# MainShunt.net
KiCad netlist of a schematic drawn in Altium Designer
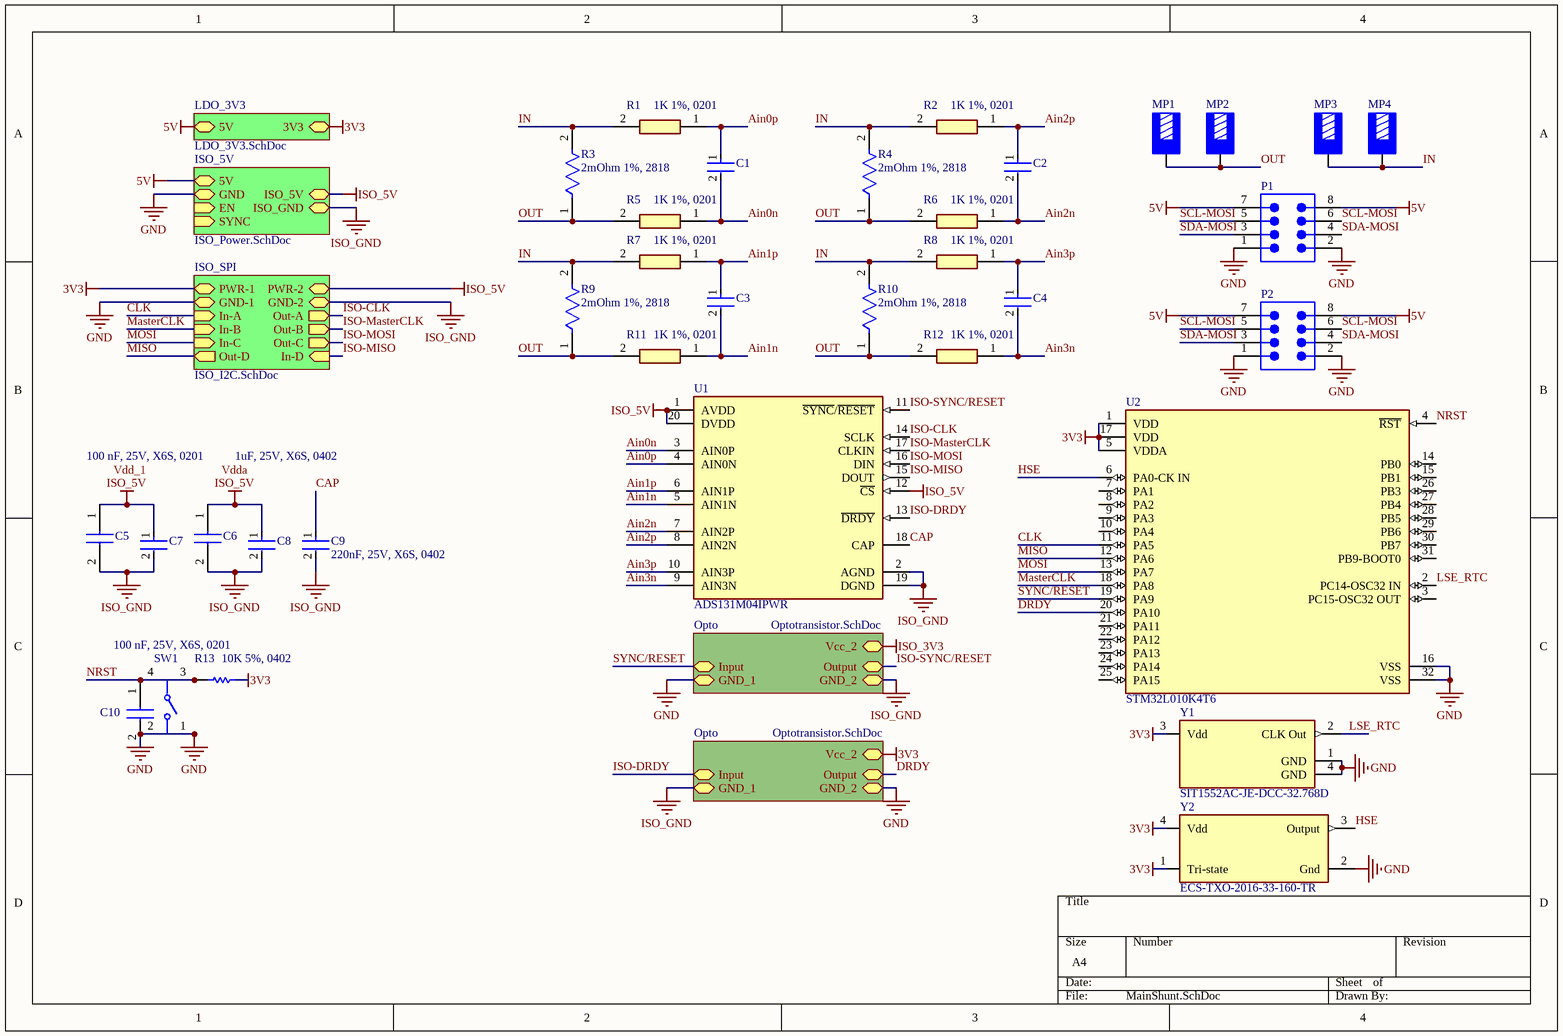
[diagram p0: MainShunt.SchDoc]

(export (version "E")
  (design (tool "Eeschema 10.0.6"))
  (components
    (comp (ref "C1")
      (value "10nF, 25V, X5R, 0201")
      (footprint "FP-GRM033-0_03-IPC_C")
      (description "Chip Multilayer Ceramic Capacitors for General Purpose, 0201, 10000pF, X5R, 15%, 10%, 25V")
      (fields (field (name "TOLERANCE") "10%") (field (name "VOLTAGE") "25V"))
      (libsource (lib "Altium Content Vault") (part "b4654b650e69147ec39a6b967a45e02"))
    )
    (comp (ref "C2")
      (value "10nF, 25V, X5R, 0201")
      (footprint "FP-GRM033-0_03-IPC_C")
      (description "Chip Multilayer Ceramic Capacitors for General Purpose, 0201, 10000pF, X5R, 15%, 10%, 25V")
      (fields (field (name "TOLERANCE") "10%") (field (name "VOLTAGE") "25V"))
      (libsource (lib "Altium Content Vault") (part "b4654b650e69147ec39a6b967a45e02"))
    )
    (comp (ref "C3")
      (value "10nF, 25V, X5R, 0201")
      (footprint "FP-GRM033-0_03-IPC_C")
      (description "Chip Multilayer Ceramic Capacitors for General Purpose, 0201, 10000pF, X5R, 15%, 10%, 25V")
      (fields (field (name "TOLERANCE") "10%") (field (name "VOLTAGE") "25V"))
      (libsource (lib "Altium Content Vault") (part "b4654b650e69147ec39a6b967a45e02"))
    )
    (comp (ref "C4")
      (value "10nF, 25V, X5R, 0201")
      (footprint "FP-GRM033-0_03-IPC_C")
      (description "Chip Multilayer Ceramic Capacitors for General Purpose, 0201, 10000pF, X5R, 15%, 10%, 25V")
      (fields (field (name "TOLERANCE") "10%") (field (name "VOLTAGE") "25V"))
      (libsource (lib "Altium Content Vault") (part "b4654b650e69147ec39a6b967a45e02"))
    )
    (comp (ref "C5")
      (value "100 nF, 25V, X6S, 0201")
      (footprint "SamacSys:CAPC0603X33N")
      (description "Capacitor")
      (fields
        (field (name "MANUFACTURER_PART_NUMBER") "GRM033C81E104KE14D")
        (field (name "MOUSER PART NUMBER") "81-GRM33C81E104KE14D")
      )
      (libsource (lib "*") (part "GRM033C81E104KE14D"))
    )
    (comp (ref "C6")
      (value "100 nF, 25V, X6S, 0201")
      (footprint "SamacSys:CAPC0603X33N")
      (description "Capacitor")
      (fields
        (field (name "MANUFACTURER_PART_NUMBER") "GRM033C81E104KE14D")
        (field (name "MOUSER PART NUMBER") "81-GRM33C81E104KE14D")
      )
      (libsource (lib "*") (part "GRM033C81E104KE14D"))
    )
    (comp (ref "C7")
      (value "1uF, 25V, X6S, 0402")
      (footprint "FP-GRT155-0_1-IPC_A")
      (description "Multi-Layer Ceramic Capacitor 1uF 25V X6S ±10% 0402 Paper T/R")
      (libsource (lib "Altium Content Vault") (part "02cd4be3c70576c341d710602a673aa"))
    )
    (comp (ref "C8")
      (value "1uF, 25V, X6S, 0402")
      (footprint "FP-GRT155-0_1-IPC_A")
      (description "Multi-Layer Ceramic Capacitor 1uF 25V X6S ±10% 0402 Paper T/R")
      (libsource (lib "Altium Content Vault") (part "02cd4be3c70576c341d710602a673aa"))
    )
    (comp (ref "C9")
      (value "220nF, 25V, X6S, 0402")
      (footprint "FP-C0603-030-0_03-IPC_B")
      (description "Multilayer Ceramic Capacitors 22nF ±10% 25V X5R SMD 0201")
      (fields (field (name "TOLERANCE") "10%"))
      (libsource (lib "Altium Content Vault") (part "02cd4be3c70576c341d710602a673aa"))
    )
    (comp (ref "C10")
      (value "100 nF, 25V, X6S, 0201")
      (footprint "SamacSys:CAPC0603X33N")
      (description "Capacitor")
      (fields
        (field (name "MANUFACTURER_PART_NUMBER") "GRM033C81E104KE14D")
        (field (name "MOUSER PART NUMBER") "81-GRM33C81E104KE14D")
      )
      (libsource (lib "*") (part "GRM033C81E104KE14D"))
    )
    (comp (ref "MP1")
      (value "7460307")
      (footprint "7460307_chemical surface")
      (description "7460307 8 Pin Power Element, Copper Zinc Alloy, 160A, M4, Vertical")
      (libsource (lib "Altium Content Vault") (part "WP-BUTR"))
    )
    (comp (ref "MP2")
      (value "7460307")
      (footprint "7460307_chemical surface")
      (description "7460307 8 Pin Power Element, Copper Zinc Alloy, 160A, M4, Vertical")
      (libsource (lib "Altium Content Vault") (part "WP-BUTR"))
    )
    (comp (ref "MP3")
      (value "7460307")
      (footprint "7460307_chemical surface")
      (description "7460307 8 Pin Power Element, Copper Zinc Alloy, 160A, M4, Vertical")
      (libsource (lib "Altium Content Vault") (part "WP-BUTR"))
    )
    (comp (ref "MP4")
      (value "7460307")
      (footprint "7460307_chemical surface")
      (description "7460307 8 Pin Power Element, Copper Zinc Alloy, 160A, M4, Vertical")
      (libsource (lib "Altium Content Vault") (part "WP-BUTR"))
    )
    (comp (ref "P1")
      (value "61200821621")
      (footprint "61200821621")
      (libsource (lib "Altium Content Vault") (part "Header_Male_2R_08P"))
    )
    (comp (ref "P2")
      (value "61200821621")
      (footprint "61200821621")
      (libsource (lib "Altium Content Vault") (part "Header_Male_2R_08P"))
    )
    (comp (ref "R1")
      (value "1K 1%, 0201")
      (footprint "SamacSys:ERJ1GN_(0201)")
      (description "Resistor")
      (fields
        (field (name "MANUFACTURER_PART_NUMBER") "ERJ-1GNF1001C")
        (field (name "MOUSER PART NUMBER") "667-ERJ-1GNF1001C")
      )
      (libsource (lib "*") (part "ERJ-1GNF1001C"))
    )
    (comp (ref "R2")
      (value "1K 1%, 0201")
      (footprint "SamacSys:ERJ1GN_(0201)")
      (description "Resistor")
      (fields
        (field (name "MANUFACTURER_PART_NUMBER") "ERJ-1GNF1001C")
        (field (name "MOUSER PART NUMBER") "667-ERJ-1GNF1001C")
      )
      (libsource (lib "*") (part "ERJ-1GNF1001C"))
    )
    (comp (ref "R3")
      (value "2mOhm 1%, 2818")
      (footprint "FP-WSHP2818-MFG")
      (description "WSHP28182L000FEB Res Metal Strip 2818 0.002 Ohm 1% 10W ±200ppm/C Pad SMD Automotive T/R")
      (fields (field (name "TOLERANCE") "1%"))
      (libsource (lib "Altium Content Vault") (part "1029c3af85768c4190bb7ad29bc67b5"))
    )
    (comp (ref "R4")
      (value "2mOhm 1%, 2818")
      (footprint "FP-WSHP2818-MFG")
      (description "WSHP28182L000FEB Res Metal Strip 2818 0.002 Ohm 1% 10W ±200ppm/C Pad SMD Automotive T/R")
      (fields (field (name "TOLERANCE") "1%"))
      (libsource (lib "Altium Content Vault") (part "1029c3af85768c4190bb7ad29bc67b5"))
    )
    (comp (ref "R5")
      (value "1K 1%, 0201")
      (footprint "SamacSys:ERJ1GN_(0201)")
      (description "Resistor")
      (fields
        (field (name "MANUFACTURER_PART_NUMBER") "ERJ-1GNF1001C")
        (field (name "MOUSER PART NUMBER") "667-ERJ-1GNF1001C")
      )
      (libsource (lib "*") (part "ERJ-1GNF1001C"))
    )
    (comp (ref "R6")
      (value "1K 1%, 0201")
      (footprint "SamacSys:ERJ1GN_(0201)")
      (description "Resistor")
      (fields
        (field (name "MANUFACTURER_PART_NUMBER") "ERJ-1GNF1001C")
        (field (name "MOUSER PART NUMBER") "667-ERJ-1GNF1001C")
      )
      (libsource (lib "*") (part "ERJ-1GNF1001C"))
    )
    (comp (ref "R7")
      (value "1K 1%, 0201")
      (footprint "SamacSys:ERJ1GN_(0201)")
      (description "Resistor")
      (fields
        (field (name "MANUFACTURER_PART_NUMBER") "ERJ-1GNF1001C")
        (field (name "MOUSER PART NUMBER") "667-ERJ-1GNF1001C")
      )
      (libsource (lib "*") (part "ERJ-1GNF1001C"))
    )
    (comp (ref "R8")
      (value "1K 1%, 0201")
      (footprint "SamacSys:ERJ1GN_(0201)")
      (description "Resistor")
      (fields
        (field (name "MANUFACTURER_PART_NUMBER") "ERJ-1GNF1001C")
        (field (name "MOUSER PART NUMBER") "667-ERJ-1GNF1001C")
      )
      (libsource (lib "*") (part "ERJ-1GNF1001C"))
    )
    (comp (ref "R9")
      (value "2mOhm 1%, 2818")
      (footprint "FP-WSHP2818-MFG")
      (description "WSHP28182L000FEB Res Metal Strip 2818 0.002 Ohm 1% 10W ±200ppm/C Pad SMD Automotive T/R")
      (fields (field (name "TOLERANCE") "1%"))
      (libsource (lib "Altium Content Vault") (part "1029c3af85768c4190bb7ad29bc67b5"))
    )
    (comp (ref "R10")
      (value "2mOhm 1%, 2818")
      (footprint "FP-WSHP2818-MFG")
      (description "WSHP28182L000FEB Res Metal Strip 2818 0.002 Ohm 1% 10W ±200ppm/C Pad SMD Automotive T/R")
      (fields (field (name "TOLERANCE") "1%"))
      (libsource (lib "Altium Content Vault") (part "1029c3af85768c4190bb7ad29bc67b5"))
    )
    (comp (ref "R11")
      (value "1K 1%, 0201")
      (footprint "SamacSys:ERJ1GN_(0201)")
      (description "Resistor")
      (fields
        (field (name "MANUFACTURER_PART_NUMBER") "ERJ-1GNF1001C")
        (field (name "MOUSER PART NUMBER") "667-ERJ-1GNF1001C")
      )
      (libsource (lib "*") (part "ERJ-1GNF1001C"))
    )
    (comp (ref "R12")
      (value "1K 1%, 0201")
      (footprint "SamacSys:ERJ1GN_(0201)")
      (description "Resistor")
      (fields
        (field (name "MANUFACTURER_PART_NUMBER") "ERJ-1GNF1001C")
        (field (name "MOUSER PART NUMBER") "667-ERJ-1GNF1001C")
      )
      (libsource (lib "*") (part "ERJ-1GNF1001C"))
    )
    (comp (ref "R13")
      (value "10K 5%, 0402")
      (footprint "RESC1005X40X25ML05T05")
      (fields (field (name "PART NUMBER") "ERJ-2GEJ103X") (field (name "MANUFACTURER") "Panasonic"))
      (libsource (lib "Altium Content Vault") (part "RES"))
    )
    (comp (ref "SW1")
      (value "PTS810SJM250SMTRLFS")
      (footprint "FP-PTS810SJM250SMTRLFS-MFG")
      (description "SWITCH TACTILE SPST-NO 0.05A 16V")
      (libsource (lib "Altium Content Vault") (part "1adf0dd01260c80cf25a44bfd6b99ba"))
    )
    (comp (ref "U1")
      (value "ADS131M04IPWR")
      (footprint "FP-PW0020A-IPC_A")
      (description "IC ADC 24BIT SIGMA-DELTA 20TSSOP")
      (libsource (lib "Altium Content Vault") (part "274e344240d9bfd31871b5cd51ae60c"))
    )
    (comp (ref "U2")
      (value "STM32L010K4T6")
      (footprint "FP-LQFP32-5V-MFG")
      (description "16/32-BITS MICROS")
      (fields
        (field (name "MANUFACTURER") "STMicroelectronics")
        (field (name "OCTOPART") "https://octopart.com/stm32l010k4t6-stmicroelectronics-96493833")
      )
      (libsource (lib "Altium Content Vault") (part "5ca08d69d3ff88643ab4764b3ac8b6a"))
    )
    (comp (ref "Y1")
      (value "SIT1552AC-JE-DCC-32.768D")
      (footprint "FP-SiT1552-J-MFG")
      (description "MEMS OSC TCXO 32.7680KHZ LVCMOS")
      (libsource (lib "Altium Content Vault") (part "3465f1ec27570957a13575eae84d1d8"))
    )
    (comp (ref "Y2")
      (value "ECS-TXO-2016-33-160-TR")
      (footprint "FP-TXO-2016-MFG")
      (description "XTAL OSC TCXO 16MHZ 3.3V SMD")
      (fields
        (field (name "MANUFACTURER") "ECS")
        (field (name "OCTOPART") "https://octopart.com/ecs-txo-2016-33-160-tr-ecs+international-102811109")
      )
      (libsource (lib "Altium Content Vault") (part "79411a1daa27f0f3cdd4759ff5fa8e9"))
    )
  )
  (nets
    (net (code "2") (name "/Ain0n") (class "Default")
      (node (ref "C1") (pin "2") (pinfunction "2_2") (pintype "passive"))
      (node (ref "R5") (pin "1") (pinfunction "1_1") (pintype "passive"))
      (node (ref "U1") (pin "3") (pinfunction "AIN0P_3") (pintype "passive"))
    )
    (net (code "3") (name "/Ain0p") (class "Default")
      (node (ref "C1") (pin "1") (pinfunction "1_1") (pintype "passive"))
      (node (ref "R1") (pin "1") (pinfunction "1_1") (pintype "passive"))
      (node (ref "U1") (pin "4") (pinfunction "AIN0N_4") (pintype "passive"))
    )
    (net (code "4") (name "/Ain1n") (class "Default")
      (node (ref "C3") (pin "2") (pinfunction "2_2") (pintype "passive"))
      (node (ref "R11") (pin "1") (pinfunction "1_1") (pintype "passive"))
      (node (ref "U1") (pin "5") (pinfunction "AIN1N_5") (pintype "passive"))
    )
    (net (code "5") (name "/Ain1p") (class "Default")
      (node (ref "C3") (pin "1") (pinfunction "1_1") (pintype "passive"))
      (node (ref "R7") (pin "1") (pinfunction "1_1") (pintype "passive"))
      (node (ref "U1") (pin "6") (pinfunction "AIN1P_6") (pintype "passive"))
    )
    (net (code "6") (name "/Ain2n") (class "Default")
      (node (ref "C2") (pin "2") (pinfunction "2_2") (pintype "passive"))
      (node (ref "R6") (pin "1") (pinfunction "1_1") (pintype "passive"))
      (node (ref "U1") (pin "7") (pinfunction "AIN2P_7") (pintype "passive"))
    )
    (net (code "7") (name "/Ain2p") (class "Default")
      (node (ref "C2") (pin "1") (pinfunction "1_1") (pintype "passive"))
      (node (ref "R2") (pin "1") (pinfunction "1_1") (pintype "passive"))
      (node (ref "U1") (pin "8") (pinfunction "AIN2N_8") (pintype "passive"))
    )
    (net (code "8") (name "/Ain3n") (class "Default")
      (node (ref "C4") (pin "2") (pinfunction "2_2") (pintype "passive"))
      (node (ref "R12") (pin "1") (pinfunction "1_1") (pintype "passive"))
      (node (ref "U1") (pin "9") (pinfunction "AIN3N_9") (pintype "passive"))
    )
    (net (code "9") (name "/Ain3p") (class "Default")
      (node (ref "C4") (pin "1") (pinfunction "1_1") (pintype "passive"))
      (node (ref "R8") (pin "1") (pinfunction "1_1") (pintype "passive"))
      (node (ref "U1") (pin "10") (pinfunction "AIN3P_10") (pintype "passive"))
    )
    (net (code "10") (name "/CAP") (class "Default")
      (node (ref "C9") (pin "1") (pinfunction "1_1") (pintype "passive"))
      (node (ref "U1") (pin "18") (pinfunction "CAP_18") (pintype "passive"))
    )
    (net (code "11") (name "/CLK") (class "Default")
      (node (ref "U2") (pin "11") (pinfunction "PA5_11") (pintype "bidirectional"))
    )
    (net (code "12") (name "/DRDY") (class "Default")
      (node (ref "U2") (pin "20") (pinfunction "PA10_20") (pintype "bidirectional"))
    )
    (net (code "14") (name "/HSE") (class "Default")
      (node (ref "U2") (pin "6") (pinfunction "PA0-CK_IN_6") (pintype "bidirectional"))
      (node (ref "Y2") (pin "3") (pinfunction "Output_3") (pintype "output"))
    )
    (net (code "15") (name "/IN") (class "Default")
      (node (ref "MP3") (pin "1") (pinfunction "1_1") (pintype "passive"))
      (node (ref "MP4") (pin "1") (pinfunction "1_1") (pintype "passive"))
      (node (ref "R1") (pin "2") (pinfunction "2_2") (pintype "passive"))
      (node (ref "R10") (pin "2") (pinfunction "2_2") (pintype "passive"))
      (node (ref "R2") (pin "2") (pinfunction "2_2") (pintype "passive"))
      (node (ref "R3") (pin "2") (pinfunction "2_2") (pintype "passive"))
      (node (ref "R4") (pin "2") (pinfunction "2_2") (pintype "passive"))
      (node (ref "R7") (pin "2") (pinfunction "2_2") (pintype "passive"))
      (node (ref "R8") (pin "2") (pinfunction "2_2") (pintype "passive"))
      (node (ref "R9") (pin "2") (pinfunction "2_2") (pintype "passive"))
    )
    (net (code "16") (name "/ISO-CLK") (class "Default")
      (node (ref "U1") (pin "14") (pinfunction "SCLK_14") (pintype "input"))
    )
    (net (code "17") (name "/ISO-DRDY") (class "Default")
      (node (ref "U1") (pin "13") (pinfunction "~{DRDY}_13") (pintype "input"))
    )
    (net (code "18") (name "/ISO-MISO") (class "Default")
      (node (ref "U1") (pin "15") (pinfunction "DOUT_15") (pintype "output"))
    )
    (net (code "19") (name "/ISO-MOSI") (class "Default")
      (node (ref "U1") (pin "16") (pinfunction "DIN_16") (pintype "input"))
    )
    (net (code "20") (name "/ISO-MasterCLK") (class "Default")
      (node (ref "U1") (pin "17") (pinfunction "CLKIN_17") (pintype "input"))
    )
    (net (code "21") (name "/ISO-SYNC{slash}RESET") (class "Default")
      (node (ref "U1") (pin "11") (pinfunction "~{SYNC}/~{RESET}_11") (pintype "input"))
    )
    (net (code "22") (name "/LSE_RTC") (class "Default")
      (node (ref "U2") (pin "2") (pinfunction "PC14-OSC32_IN_2") (pintype "bidirectional"))
      (node (ref "Y1") (pin "2") (pinfunction "CLK_Out_2") (pintype "output"))
    )
    (net (code "23") (name "/MISO") (class "Default")
      (node (ref "U2") (pin "12") (pinfunction "PA6_12") (pintype "bidirectional"))
    )
    (net (code "24") (name "/MOSI") (class "Default")
      (node (ref "U2") (pin "13") (pinfunction "PA7_13") (pintype "bidirectional"))
    )
    (net (code "25") (name "/MasterCLK") (class "Default")
      (node (ref "U2") (pin "18") (pinfunction "PA8_18") (pintype "bidirectional"))
    )
    (net (code "26") (name "/NRST") (class "Default")
      (node (ref "C10") (pin "1") (pinfunction "1_1") (pintype "passive"))
      (node (ref "R13") (pin "2") (pinfunction "2_2") (pintype "passive"))
      (node (ref "SW1") (pin "3") (pinfunction "3_3") (pintype "passive"))
      (node (ref "SW1") (pin "4") (pinfunction "4_4") (pintype "passive"))
      (node (ref "U2") (pin "4") (pinfunction "~{RST}_4") (pintype "input"))
    )
    (net (code "27") (name "/OUT") (class "Default")
      (node (ref "MP1") (pin "1") (pinfunction "1_1") (pintype "passive"))
      (node (ref "MP2") (pin "1") (pinfunction "1_1") (pintype "passive"))
      (node (ref "R10") (pin "1") (pinfunction "1_1") (pintype "passive"))
      (node (ref "R11") (pin "2") (pinfunction "2_2") (pintype "passive"))
      (node (ref "R12") (pin "2") (pinfunction "2_2") (pintype "passive"))
      (node (ref "R3") (pin "1") (pinfunction "1_1") (pintype "passive"))
      (node (ref "R4") (pin "1") (pinfunction "1_1") (pintype "passive"))
      (node (ref "R5") (pin "2") (pinfunction "2_2") (pintype "passive"))
      (node (ref "R6") (pin "2") (pinfunction "2_2") (pintype "passive"))
      (node (ref "R9") (pin "1") (pinfunction "1_1") (pintype "passive"))
    )
    (net (code "28") (name "/SCL-MOSI") (class "Default")
      (node (ref "P1") (pin "5") (pinfunction "5_5") (pintype "passive"))
      (node (ref "P1") (pin "6") (pinfunction "6_6") (pintype "passive"))
      (node (ref "P2") (pin "5") (pinfunction "5_5") (pintype "passive"))
      (node (ref "P2") (pin "6") (pinfunction "6_6") (pintype "passive"))
    )
    (net (code "29") (name "/SDA-MOSI") (class "Default")
      (node (ref "P1") (pin "3") (pinfunction "3_3") (pintype "passive"))
      (node (ref "P1") (pin "4") (pinfunction "4_4") (pintype "passive"))
      (node (ref "P2") (pin "3") (pinfunction "3_3") (pintype "passive"))
      (node (ref "P2") (pin "4") (pinfunction "4_4") (pintype "passive"))
    )
    (net (code "31") (name "/SYNC{slash}RESET") (class "Default")
      (node (ref "U2") (pin "19") (pinfunction "PA9_19") (pintype "bidirectional"))
    )
    (net (code "32") (name "3V3") (class "Default")
      (node (ref "R13") (pin "1") (pinfunction "1_1") (pintype "passive"))
      (node (ref "U2") (pin "1") (pinfunction "VDD_1") (pintype "power_in"))
      (node (ref "U2") (pin "17") (pinfunction "VDD_17") (pintype "power_in"))
      (node (ref "U2") (pin "5") (pinfunction "VDDA_5") (pintype "power_in"))
      (node (ref "Y1") (pin "3") (pinfunction "Vdd_3") (pintype "power_in"))
      (node (ref "Y2") (pin "1") (pinfunction "Tri-state_1") (pintype "passive"))
      (node (ref "Y2") (pin "4") (pinfunction "Vdd_4") (pintype "power_in"))
    )
    (net (code "33") (name "5V") (class "Default")
      (node (ref "P1") (pin "7") (pinfunction "7_7") (pintype "passive"))
      (node (ref "P1") (pin "8") (pinfunction "8_8") (pintype "passive"))
      (node (ref "P2") (pin "7") (pinfunction "7_7") (pintype "passive"))
      (node (ref "P2") (pin "8") (pinfunction "8_8") (pintype "passive"))
    )
    (net (code "34") (name "GND") (class "Default")
      (node (ref "C10") (pin "2") (pinfunction "2_2") (pintype "passive"))
      (node (ref "P1") (pin "1") (pinfunction "1_1") (pintype "passive"))
      (node (ref "P1") (pin "2") (pinfunction "2_2") (pintype "passive"))
      (node (ref "P2") (pin "1") (pinfunction "1_1") (pintype "passive"))
      (node (ref "P2") (pin "2") (pinfunction "2_2") (pintype "passive"))
      (node (ref "SW1") (pin "1") (pinfunction "1_1") (pintype "passive"))
      (node (ref "SW1") (pin "2") (pinfunction "2_2") (pintype "passive"))
      (node (ref "U2") (pin "16") (pinfunction "VSS_16") (pintype "power_in"))
      (node (ref "U2") (pin "32") (pinfunction "VSS_32") (pintype "power_in"))
      (node (ref "Y1") (pin "1") (pinfunction "GND_1") (pintype "power_in"))
      (node (ref "Y1") (pin "4") (pinfunction "GND_4") (pintype "power_in"))
      (node (ref "Y2") (pin "2") (pinfunction "Gnd_2") (pintype "power_in"))
    )
    (net (code "36") (name "ISO_5V") (class "Default")
      (node (ref "C5") (pin "1") (pinfunction "1_1") (pintype "passive"))
      (node (ref "C6") (pin "1") (pinfunction "1_1") (pintype "passive"))
      (node (ref "C7") (pin "1") (pinfunction "1_1") (pintype "passive"))
      (node (ref "C8") (pin "1") (pinfunction "1_1") (pintype "passive"))
      (node (ref "U1") (pin "1") (pinfunction "AVDD_1") (pintype "power_in"))
      (node (ref "U1") (pin "12") (pinfunction "~{CS}_12") (pintype "input"))
      (node (ref "U1") (pin "20") (pinfunction "DVDD_20") (pintype "power_in"))
    )
    (net (code "37") (name "ISO_GND") (class "Default")
      (node (ref "C5") (pin "2") (pinfunction "2_2") (pintype "passive"))
      (node (ref "C6") (pin "2") (pinfunction "2_2") (pintype "passive"))
      (node (ref "C7") (pin "2") (pinfunction "2_2") (pintype "passive"))
      (node (ref "C8") (pin "2") (pinfunction "2_2") (pintype "passive"))
      (node (ref "C9") (pin "2") (pinfunction "2_2") (pintype "passive"))
      (node (ref "U1") (pin "19") (pinfunction "DGND_19") (pintype "power_in"))
      (node (ref "U1") (pin "2") (pinfunction "AGND_2") (pintype "power_in"))
    )
    (net (code "38") (name "unconnected-(U2-PA1-Pad7)") (class "Default")
      (node (ref "U2") (pin "7") (pinfunction "PA1_7") (pintype "bidirectional"))
    )
    (net (code "39") (name "unconnected-(U2-PA2-Pad8)") (class "Default")
      (node (ref "U2") (pin "8") (pinfunction "PA2_8") (pintype "bidirectional"))
    )
    (net (code "40") (name "unconnected-(U2-PA3-Pad9)") (class "Default")
      (node (ref "U2") (pin "9") (pinfunction "PA3_9") (pintype "bidirectional"))
    )
    (net (code "41") (name "unconnected-(U2-PA4-Pad10)") (class "Default")
      (node (ref "U2") (pin "10") (pinfunction "PA4_10") (pintype "bidirectional"))
    )
    (net (code "42") (name "unconnected-(U2-PA11-Pad21)") (class "Default")
      (node (ref "U2") (pin "21") (pinfunction "PA11_21") (pintype "bidirectional"))
    )
    (net (code "43") (name "unconnected-(U2-PA12-Pad22)") (class "Default")
      (node (ref "U2") (pin "22") (pinfunction "PA12_22") (pintype "bidirectional"))
    )
    (net (code "44") (name "unconnected-(U2-PA13-Pad23)") (class "Default")
      (node (ref "U2") (pin "23") (pinfunction "PA13_23") (pintype "bidirectional"))
    )
    (net (code "45") (name "unconnected-(U2-PA14-Pad24)") (class "Default")
      (node (ref "U2") (pin "24") (pinfunction "PA14_24") (pintype "bidirectional"))
    )
    (net (code "46") (name "unconnected-(U2-PA15-Pad25)") (class "Default")
      (node (ref "U2") (pin "25") (pinfunction "PA15_25") (pintype "bidirectional"))
    )
    (net (code "47") (name "unconnected-(U2-PB0-Pad14)") (class "Default")
      (node (ref "U2") (pin "14") (pinfunction "PB0_14") (pintype "bidirectional"))
    )
    (net (code "48") (name "unconnected-(U2-PB1-Pad15)") (class "Default")
      (node (ref "U2") (pin "15") (pinfunction "PB1_15") (pintype "bidirectional"))
    )
    (net (code "49") (name "unconnected-(U2-PB3-Pad26)") (class "Default")
      (node (ref "U2") (pin "26") (pinfunction "PB3_26") (pintype "bidirectional"))
    )
    (net (code "50") (name "unconnected-(U2-PB4-Pad27)") (class "Default")
      (node (ref "U2") (pin "27") (pinfunction "PB4_27") (pintype "bidirectional"))
    )
    (net (code "51") (name "unconnected-(U2-PB5-Pad28)") (class "Default")
      (node (ref "U2") (pin "28") (pinfunction "PB5_28") (pintype "bidirectional"))
    )
    (net (code "52") (name "unconnected-(U2-PB6-Pad29)") (class "Default")
      (node (ref "U2") (pin "29") (pinfunction "PB6_29") (pintype "bidirectional"))
    )
    (net (code "53") (name "unconnected-(U2-PB7-Pad30)") (class "Default")
      (node (ref "U2") (pin "30") (pinfunction "PB7_30") (pintype "bidirectional"))
    )
    (net (code "54") (name "unconnected-(U2-PB9-BOOT0-Pad31)") (class "Default")
      (node (ref "U2") (pin "31") (pinfunction "PB9-BOOT0_31") (pintype "bidirectional"))
    )
    (net (code "55") (name "unconnected-(U2-PC15-OSC32_OUT-Pad3)") (class "Default")
      (node (ref "U2") (pin "3") (pinfunction "PC15-OSC32_OUT_3") (pintype "bidirectional"))
    )
  )
)
